# comeNCap.net
KiCad netlist of a schematic drawn in EAGLE
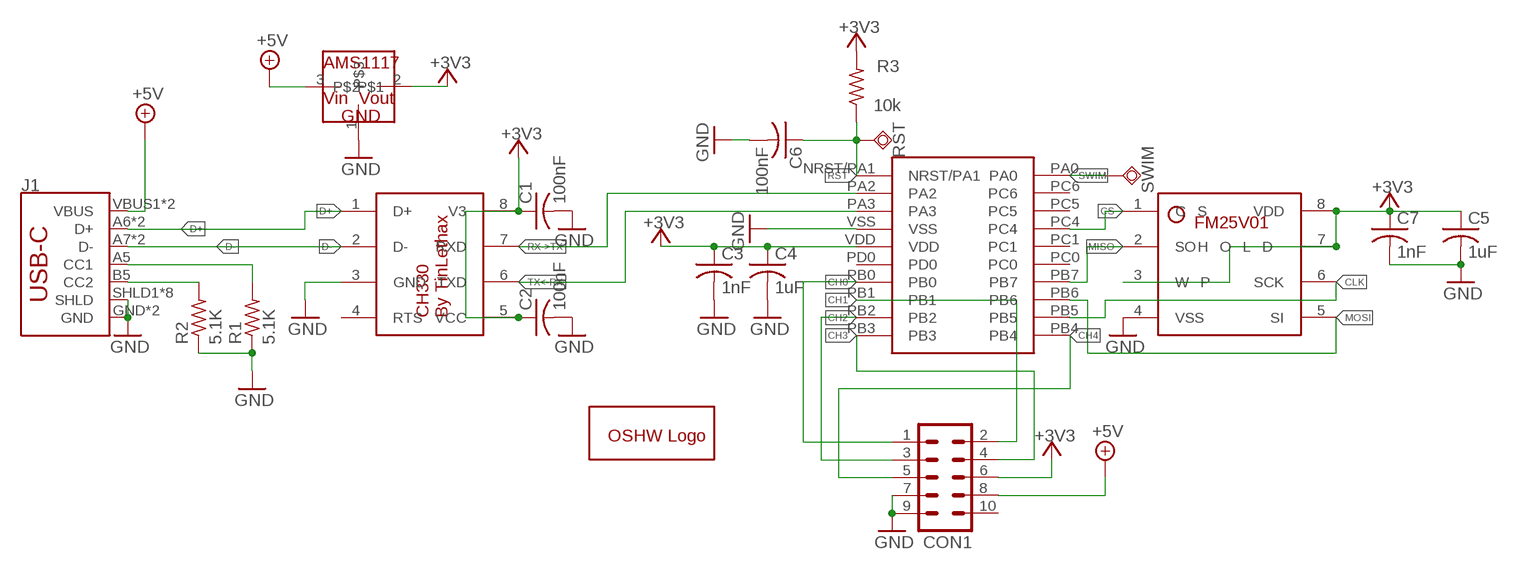
[diagram p0: schematic, sheet 1]

(export (version "E")
  (design (tool "Eeschema 10.0.6"))
  (components
    (comp (ref "C1")
      (value "100nF")
      (footprint "eagle-import:C1210")
      (libsource (lib "eagle-import") (part "C-USC1210"))
    )
    (comp (ref "C2")
      (value "100nF")
      (footprint "eagle-import:C1210")
      (libsource (lib "eagle-import") (part "C-USC1210"))
    )
    (comp (ref "C3")
      (value "1nF")
      (footprint "eagle-import:C0805")
      (libsource (lib "eagle-import") (part "C-USC0805"))
    )
    (comp (ref "C4")
      (value "1uF")
      (footprint "eagle-import:C0603")
      (libsource (lib "eagle-import") (part "C-USC0603"))
    )
    (comp (ref "C5")
      (value "1uF")
      (footprint "eagle-import:C0603")
      (libsource (lib "eagle-import") (part "C-USC0603"))
    )
    (comp (ref "C6")
      (value "100nF")
      (footprint "eagle-import:C1210")
      (libsource (lib "eagle-import") (part "C-USC1210"))
    )
    (comp (ref "C7")
      (value "1nF")
      (footprint "eagle-import:C0805")
      (libsource (lib "eagle-import") (part "C-USC0805"))
    )
    (comp (ref "CON1")
      (value "MA05-2")
      (footprint "eagle-import:MA05-2")
      (libsource (lib "eagle-import") (part "MA05-2"))
    )
    (comp (ref "GOLD_ORB_SM1")
      (value "OSHWLOGOLOGO5MM")
      (footprint "eagle-import:OSHW_5MM")
      (libsource (lib "eagle-import") (part "OSHWLOGOLOGO5MM"))
    )
    (comp (ref "J1")
      (value "USB_C16PIN")
      (footprint "eagle-import:USB-C-16P")
      (libsource (lib "eagle-import") (part "USB_C16PIN"))
    )
    (comp (ref "R1")
      (value "5.1K")
      (footprint "eagle-import:R0805")
      (libsource (lib "eagle-import") (part "R-US_R0805"))
    )
    (comp (ref "R2")
      (value "5.1K")
      (footprint "eagle-import:R0805")
      (libsource (lib "eagle-import") (part "R-US_R0805"))
    )
    (comp (ref "R3")
      (value "10k")
      (footprint "eagle-import:R0805")
      (libsource (lib "eagle-import") (part "R-US_R0805"))
    )
    (comp (ref "RST")
      (value "TPSQTP20R")
      (footprint "eagle-import:TP20R")
      (libsource (lib "eagle-import") (part "TPSQTP20R"))
    )
    (comp (ref "SWIM")
      (value "TPSQTP20R")
      (footprint "eagle-import:TP20R")
      (libsource (lib "eagle-import") (part "TPSQTP20R"))
    )
    (comp (ref "U$1")
      (value "STM8L151F3")
      (footprint "eagle-import:UFQFPN-20")
      (libsource (lib "eagle-import") (part "STM8L151F3"))
    )
    (comp (ref "U$2")
      (value "FM25V01")
      (footprint "eagle-import:SOIC127P601X172-8N")
      (fields (field (name "PARTNO") "FM52V01"))
      (libsource (lib "eagle-import") (part "FM25V01"))
    )
    (comp (ref "U$3")
      (value "CH330")
      (footprint "eagle-import:SOIC127P600X150-8N")
      (libsource (lib "eagle-import") (part "CH330"))
    )
    (comp (ref "U$4")
      (value "AMS1117")
      (footprint "eagle-import:SOT223")
      (libsource (lib "eagle-import") (part "AMS1117"))
    )
  )
  (nets
    (net (code "1") (name "+3V3") (class "Default")
      (node (ref "C1") (pin "1") (pinfunction "1_1") (pintype "passive"))
      (node (ref "C2") (pin "1") (pinfunction "1_1") (pintype "passive"))
      (node (ref "C3") (pin "1") (pinfunction "1_1") (pintype "passive"))
      (node (ref "C4") (pin "1") (pinfunction "1_1") (pintype "passive"))
      (node (ref "C5") (pin "1") (pinfunction "1_1") (pintype "passive"))
      (node (ref "C7") (pin "1") (pinfunction "1_1") (pintype "passive"))
      (node (ref "CON1") (pin "6") (pinfunction "6_6") (pintype "passive"))
      (node (ref "R3") (pin "2") (pinfunction "2_2") (pintype "passive"))
      (node (ref "U$1") (pin "VDD") (pinfunction "VDD_VDD") (pintype "bidirectional"))
      (node (ref "U$2") (pin "3") (pinfunction "W̅P̅_3") (pintype "bidirectional"))
      (node (ref "U$2") (pin "7") (pinfunction "H̅O̅L̅D̅_7") (pintype "bidirectional"))
      (node (ref "U$2") (pin "8") (pinfunction "VDD_8") (pintype "bidirectional"))
      (node (ref "U$3") (pin "5") (pinfunction "VCC_5") (pintype "bidirectional"))
      (node (ref "U$3") (pin "8") (pinfunction "V3_8") (pintype "bidirectional"))
      (node (ref "U$4") (pin "2") (pinfunction "P$2_2") (pintype "bidirectional"))
    )
    (net (code "2") (name "+5V") (class "Default")
      (node (ref "CON1") (pin "8") (pinfunction "8_8") (pintype "passive"))
      (node (ref "J1") (pin "VBUS1") (pinfunction "VBUS_VBUS1") (pintype "bidirectional"))
      (node (ref "J1") (pin "VBUS2") (pinfunction "VBUS_VBUS2") (pintype "bidirectional"))
      (node (ref "U$4") (pin "3") (pinfunction "P$1_3") (pintype "bidirectional"))
    )
    (net (code "3") (name "CH0") (class "Default")
      (node (ref "CON1") (pin "1") (pinfunction "1_1") (pintype "passive"))
      (node (ref "U$1") (pin "PB0") (pinfunction "PB0_PB0") (pintype "bidirectional"))
    )
    (net (code "4") (name "CH1") (class "Default")
      (node (ref "CON1") (pin "2") (pinfunction "2_2") (pintype "passive"))
      (node (ref "U$1") (pin "PB1") (pinfunction "PB1_PB1") (pintype "bidirectional"))
    )
    (net (code "5") (name "CH2") (class "Default")
      (node (ref "CON1") (pin "3") (pinfunction "3_3") (pintype "passive"))
      (node (ref "U$1") (pin "PB2") (pinfunction "PB2_PB2") (pintype "bidirectional"))
    )
    (net (code "6") (name "CH3") (class "Default")
      (node (ref "CON1") (pin "4") (pinfunction "4_4") (pintype "passive"))
      (node (ref "U$1") (pin "PB3") (pinfunction "PB3_PB3") (pintype "bidirectional"))
    )
    (net (code "7") (name "CH4") (class "Default")
      (node (ref "CON1") (pin "5") (pinfunction "5_5") (pintype "passive"))
      (node (ref "U$1") (pin "PB4") (pinfunction "PB4_PB4") (pintype "bidirectional"))
    )
    (net (code "8") (name "CLK") (class "Default")
      (node (ref "U$1") (pin "PB5") (pinfunction "PB5_PB5") (pintype "bidirectional"))
      (node (ref "U$2") (pin "6") (pinfunction "SCK_6") (pintype "bidirectional"))
    )
    (net (code "9") (name "CS") (class "Default")
      (node (ref "U$1") (pin "PC4") (pinfunction "PC4_PC4") (pintype "bidirectional"))
      (node (ref "U$2") (pin "1") (pinfunction "C̅S̅_1") (pintype "bidirectional"))
    )
    (net (code "10") (name "D+") (class "Default")
      (node (ref "J1") (pin "A6") (pinfunction "D+_A6") (pintype "bidirectional"))
      (node (ref "J1") (pin "B6") (pinfunction "D+_B6") (pintype "bidirectional"))
      (node (ref "U$3") (pin "1") (pinfunction "D+_1") (pintype "bidirectional"))
    )
    (net (code "11") (name "D-") (class "Default")
      (node (ref "J1") (pin "A7") (pinfunction "D-_A7") (pintype "bidirectional"))
      (node (ref "J1") (pin "B7") (pinfunction "D-_B7") (pintype "bidirectional"))
      (node (ref "U$3") (pin "2") (pinfunction "D-_2") (pintype "bidirectional"))
    )
    (net (code "12") (name "GND") (class "Default")
      (node (ref "C1") (pin "2") (pinfunction "2_2") (pintype "passive"))
      (node (ref "C2") (pin "2") (pinfunction "2_2") (pintype "passive"))
      (node (ref "C3") (pin "2") (pinfunction "2_2") (pintype "passive"))
      (node (ref "C4") (pin "2") (pinfunction "2_2") (pintype "passive"))
      (node (ref "C5") (pin "2") (pinfunction "2_2") (pintype "passive"))
      (node (ref "C6") (pin "2") (pinfunction "2_2") (pintype "passive"))
      (node (ref "C7") (pin "2") (pinfunction "2_2") (pintype "passive"))
      (node (ref "CON1") (pin "7") (pinfunction "7_7") (pintype "passive"))
      (node (ref "CON1") (pin "9") (pinfunction "9_9") (pintype "passive"))
      (node (ref "J1") (pin "GND") (pinfunction "GND_GND") (pintype "bidirectional"))
      (node (ref "J1") (pin "GND2") (pinfunction "GND_GND2") (pintype "bidirectional"))
      (node (ref "J1") (pin "SHLD1") (pinfunction "SHLD_SHLD1") (pintype "bidirectional"))
      (node (ref "J1") (pin "SHLD2") (pinfunction "SHLD_SHLD2") (pintype "bidirectional"))
      (node (ref "J1") (pin "SHLD3") (pinfunction "SHLD_SHLD3") (pintype "bidirectional"))
      (node (ref "J1") (pin "SHLD4") (pinfunction "SHLD_SHLD4") (pintype "bidirectional"))
      (node (ref "J1") (pin "SHLD5") (pinfunction "SHLD_SHLD5") (pintype "bidirectional"))
      (node (ref "J1") (pin "SHLD6") (pinfunction "SHLD_SHLD6") (pintype "bidirectional"))
      (node (ref "J1") (pin "SHLD7") (pinfunction "SHLD_SHLD7") (pintype "bidirectional"))
      (node (ref "J1") (pin "SHLD8") (pinfunction "SHLD_SHLD8") (pintype "bidirectional"))
      (node (ref "R1") (pin "1") (pinfunction "1_1") (pintype "passive"))
      (node (ref "R2") (pin "1") (pinfunction "1_1") (pintype "passive"))
      (node (ref "U$1") (pin "VSS") (pinfunction "VSS_VSS") (pintype "bidirectional"))
      (node (ref "U$2") (pin "4") (pinfunction "VSS_4") (pintype "bidirectional"))
      (node (ref "U$3") (pin "3") (pinfunction "GND_3") (pintype "bidirectional"))
      (node (ref "U$4") (pin "1") (pinfunction "P$3_1") (pintype "bidirectional"))
    )
    (net (code "13") (name "MISO") (class "Default")
      (node (ref "U$1") (pin "PB7") (pinfunction "PB7_PB7") (pintype "bidirectional"))
      (node (ref "U$2") (pin "2") (pinfunction "SO_2") (pintype "bidirectional"))
    )
    (net (code "14") (name "MOSI") (class "Default")
      (node (ref "U$1") (pin "PB6") (pinfunction "PB6_PB6") (pintype "bidirectional"))
      (node (ref "U$2") (pin "5") (pinfunction "SI_5") (pintype "bidirectional"))
    )
    (net (code "15") (name "Net-(J1-CC1)") (class "Default")
      (node (ref "J1") (pin "A5") (pinfunction "CC1_A5") (pintype "bidirectional"))
      (node (ref "R1") (pin "2") (pinfunction "2_2") (pintype "passive"))
    )
    (net (code "16") (name "Net-(J1-CC2)") (class "Default")
      (node (ref "J1") (pin "B5") (pinfunction "CC2_B5") (pintype "bidirectional"))
      (node (ref "R2") (pin "2") (pinfunction "2_2") (pintype "passive"))
    )
    (net (code "17") (name "RST") (class "Default")
      (node (ref "C6") (pin "1") (pinfunction "1_1") (pintype "passive"))
      (node (ref "R3") (pin "1") (pinfunction "1_1") (pintype "passive"))
      (node (ref "RST") (pin "TP") (pinfunction "TP_TP") (pintype "input"))
      (node (ref "U$1") (pin "NRST/PA1") (pinfunction "NRST/PA1_NRST/PA1") (pintype "bidirectional"))
    )
    (net (code "18") (name "RX->TX") (class "Default")
      (node (ref "U$1") (pin "PA2") (pinfunction "PA2_PA2") (pintype "bidirectional"))
      (node (ref "U$3") (pin "7") (pinfunction "RXD_7") (pintype "bidirectional"))
    )
    (net (code "19") (name "SWIM") (class "Default")
      (node (ref "SWIM") (pin "TP") (pinfunction "TP_TP") (pintype "input"))
      (node (ref "U$1") (pin "PA0") (pinfunction "PA0_PA0") (pintype "bidirectional"))
    )
    (net (code "20") (name "TX<-RX") (class "Default")
      (node (ref "U$1") (pin "PA3") (pinfunction "PA3_PA3") (pintype "bidirectional"))
      (node (ref "U$3") (pin "6") (pinfunction "TXD_6") (pintype "bidirectional"))
    )
    (net (code "21") (name "unconnected-(CON1-Pad10)") (class "Default")
      (node (ref "CON1") (pin "10") (pinfunction "10_10") (pintype "passive"))
    )
    (net (code "22") (name "unconnected-(U$1-PadPC0)") (class "Default")
      (node (ref "U$1") (pin "PC0") (pinfunction "PC0_PC0") (pintype "bidirectional"))
    )
    (net (code "23") (name "unconnected-(U$1-PadPC1)") (class "Default")
      (node (ref "U$1") (pin "PC1") (pinfunction "PC1_PC1") (pintype "bidirectional"))
    )
    (net (code "24") (name "unconnected-(U$1-PadPC5)") (class "Default")
      (node (ref "U$1") (pin "PC5") (pinfunction "PC5_PC5") (pintype "bidirectional"))
    )
    (net (code "25") (name "unconnected-(U$1-PadPC6)") (class "Default")
      (node (ref "U$1") (pin "PC6") (pinfunction "PC6_PC6") (pintype "bidirectional"))
    )
    (net (code "26") (name "unconnected-(U$1-PadPD0)") (class "Default")
      (node (ref "U$1") (pin "PD0") (pinfunction "PD0_PD0") (pintype "bidirectional"))
    )
    (net (code "27") (name "unconnected-(U$3-RTS-Pad4)") (class "Default")
      (node (ref "U$3") (pin "4") (pinfunction "RTS_4") (pintype "bidirectional"))
    )
  )
)
